# satshakit_modular.net
KiCad netlist of a schematic drawn in EAGLE
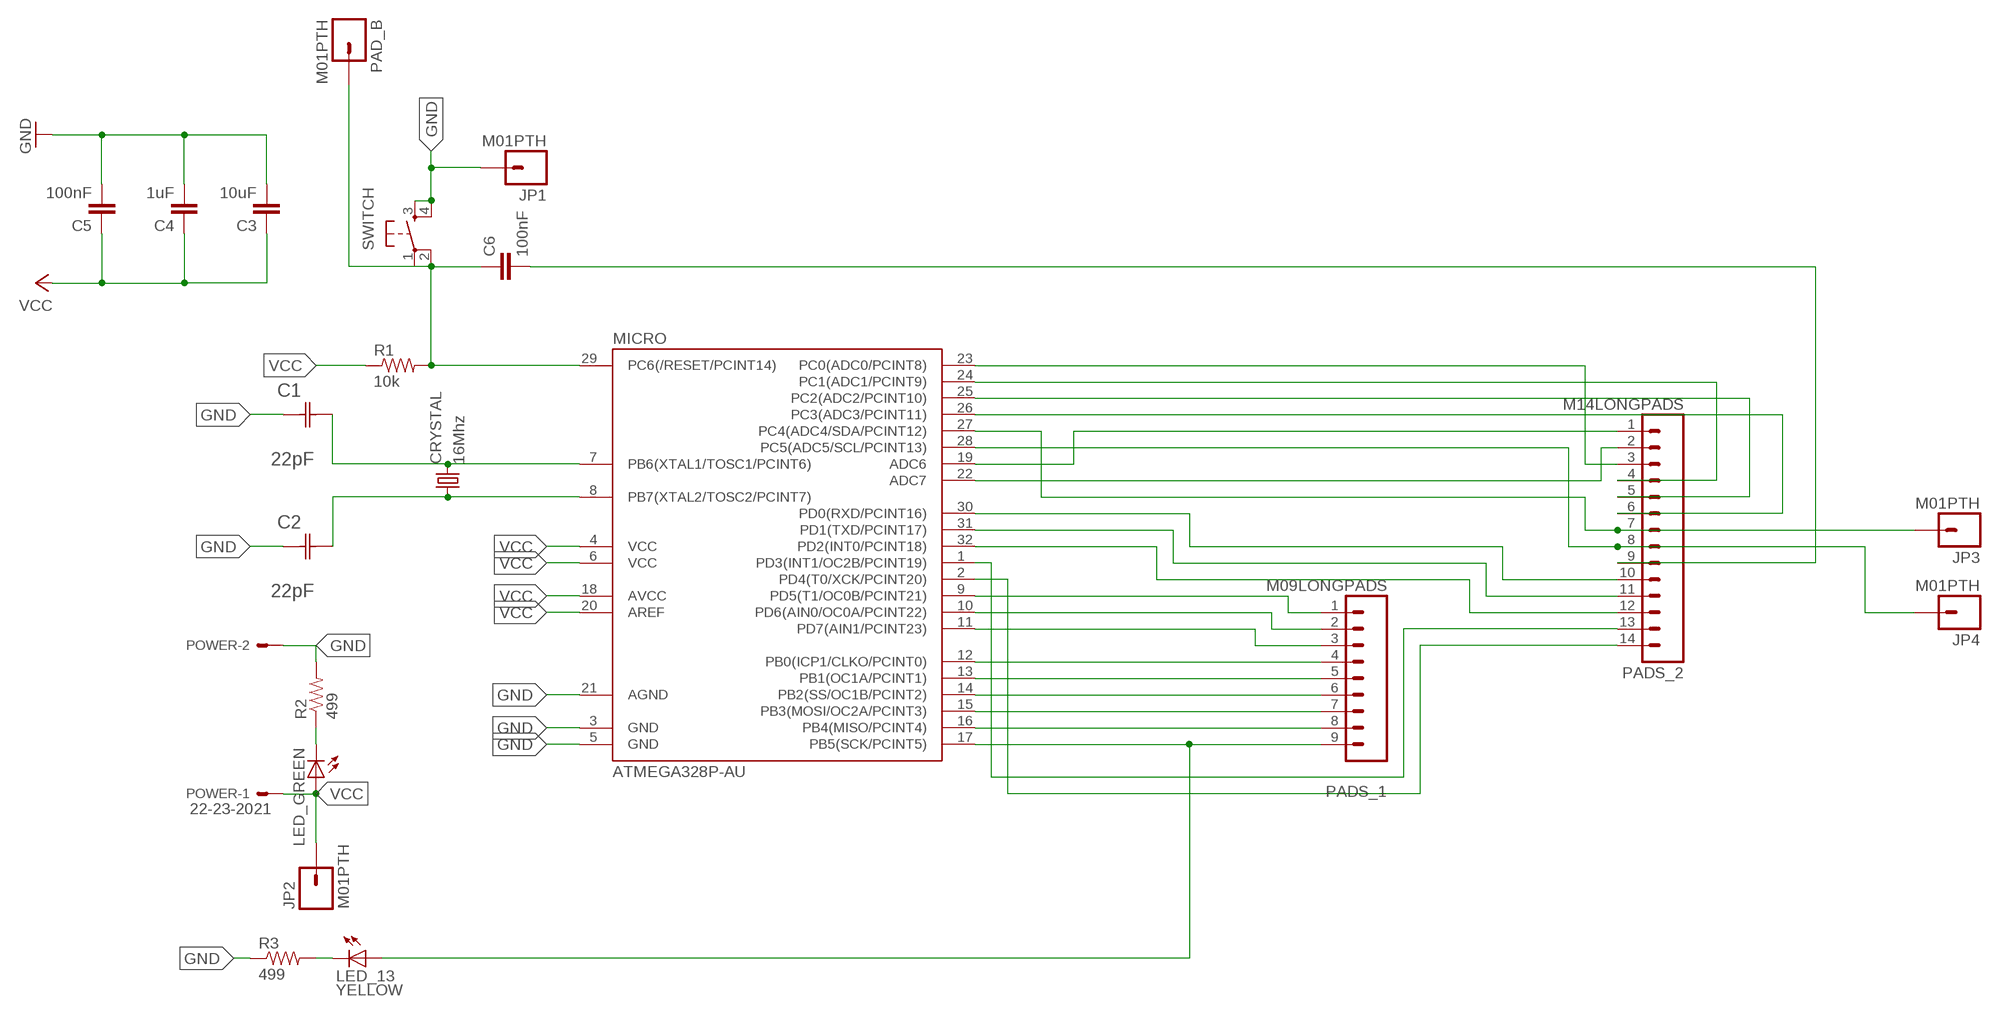
[diagram p0: schematic, sheet 1]

(export (version "E")
  (design (tool "Eeschema 10.0.6"))
  (components
    (comp (ref "C1")
      (value "22pF")
      (footprint "eagle-import:CAPC3216X178N")
      (fields (field (name "MPN") "0612ZC225MAT2A") (field (name "TOLERANCE") "±20%"))
      (libsource (lib "eagle-import") (part "0612ZC225MAT2A"))
    )
    (comp (ref "C2")
      (value "22pF")
      (footprint "eagle-import:CAPC3216X178N")
      (fields (field (name "MPN") "0612ZC225MAT2A") (field (name "TOLERANCE") "±20%"))
      (libsource (lib "eagle-import") (part "0612ZC225MAT2A"))
    )
    (comp (ref "C3")
      (value "10uF")
      (footprint "eagle-import:1206")
      (libsource (lib "eagle-import") (part "CAP1206"))
    )
    (comp (ref "C4")
      (value "1uF")
      (footprint "eagle-import:1206")
      (libsource (lib "eagle-import") (part "CAP1206"))
    )
    (comp (ref "C5")
      (value "100nF")
      (footprint "eagle-import:1206")
      (libsource (lib "eagle-import") (part "CAP1206"))
    )
    (comp (ref "C6")
      (value "100nF")
      (footprint "eagle-import:1206")
      (libsource (lib "eagle-import") (part "CAP1206"))
    )
    (comp (ref "CRYSTAL")
      (value "16Mhz")
      (footprint "eagle-import:CSM-7X-DU")
      (libsource (lib "eagle-import") (part "CSM-7X-DU"))
    )
    (comp (ref "JP1")
      (value "M01PTH")
      (footprint "eagle-import:1X01")
      (libsource (lib "eagle-import") (part "M01PTH"))
    )
    (comp (ref "JP2")
      (value "M01PTH")
      (footprint "eagle-import:1X01")
      (libsource (lib "eagle-import") (part "M01PTH"))
    )
    (comp (ref "JP3")
      (value "M01PTH")
      (footprint "eagle-import:1X01")
      (libsource (lib "eagle-import") (part "M01PTH"))
    )
    (comp (ref "JP4")
      (value "M01PTH")
      (footprint "eagle-import:1X01")
      (libsource (lib "eagle-import") (part "M01PTH"))
    )
    (comp (ref "LED_13")
      (value "YELLOW")
      (footprint "eagle-import:1206")
      (libsource (lib "eagle-import") (part "LED1206"))
    )
    (comp (ref "LED_GREEN")
      (value "LED1206")
      (footprint "eagle-import:1206")
      (libsource (lib "eagle-import") (part "LED1206"))
    )
    (comp (ref "MICRO")
      (value "ATMEGA328P-AU")
      (footprint "eagle-import:TQFP32-08")
      (libsource (lib "eagle-import") (part "ATMEGA48/88/168-AU"))
    )
    (comp (ref "PADS_1")
      (value "M09LONGPADS")
      (footprint "eagle-import:1X09_LONGPADS")
      (libsource (lib "eagle-import") (part "M09LONGPADS"))
    )
    (comp (ref "PADS_2")
      (value "M14LONGPADS")
      (footprint "eagle-import:1X14-LONGPADS")
      (libsource (lib "eagle-import") (part "M14LONGPADS"))
    )
    (comp (ref "PAD_B")
      (value "M01PTH")
      (footprint "eagle-import:1X01")
      (libsource (lib "eagle-import") (part "M01PTH"))
    )
    (comp (ref "POWER")
      (value "22-23-2021")
      (footprint "eagle-import:22-23-2021")
      (fields (field (name "MF") "MOLEX"))
      (libsource (lib "eagle-import") (part "22-23-2021"))
    )
    (comp (ref "R1")
      (value "10k")
      (footprint "eagle-import:1206")
      (libsource (lib "eagle-import") (part "RESISTOR1206"))
    )
    (comp (ref "R2")
      (value "499")
      (footprint "eagle-import:1206")
      (libsource (lib "eagle-import") (part "RESISTOR1206"))
    )
    (comp (ref "R3")
      (value "499")
      (footprint "eagle-import:1206")
      (libsource (lib "eagle-import") (part "RESISTOR1206"))
    )
    (comp (ref "SWITCH")
      (value "6MM_SWITCH6MM_SWITCH")
      (footprint "eagle-import:6MM_SWITCH")
      (libsource (lib "eagle-import") (part "6MM_SWITCH6MM_SWITCH"))
    )
  )
  (nets
    (net (code "1") (name "GND") (class "Default")
      (node (ref "C1") (pin "1") (pinfunction "C1_1") (pintype "passive"))
      (node (ref "C2") (pin "1") (pinfunction "C1_1") (pintype "passive"))
      (node (ref "C3") (pin "2") (pinfunction "2_2") (pintype "passive"))
      (node (ref "C4") (pin "2") (pinfunction "2_2") (pintype "passive"))
      (node (ref "C5") (pin "2") (pinfunction "2_2") (pintype "passive"))
      (node (ref "JP1") (pin "1") (pinfunction "1_1") (pintype "passive"))
      (node (ref "MICRO") (pin "21") (pinfunction "AGND_21") (pintype "power_in"))
      (node (ref "MICRO") (pin "3") (pinfunction "GND_3") (pintype "power_in"))
      (node (ref "MICRO") (pin "5") (pinfunction "GND_5") (pintype "power_in"))
      (node (ref "POWER") (pin "2") (pinfunction "S_2") (pintype "passive"))
      (node (ref "R2") (pin "2") (pinfunction "2_2") (pintype "passive"))
      (node (ref "R3") (pin "1") (pinfunction "1_1") (pintype "passive"))
      (node (ref "SWITCH") (pin "3") (pinfunction "S_3") (pintype "passive"))
      (node (ref "SWITCH") (pin "4") (pinfunction "S1_4") (pintype "passive"))
    )
    (net (code "2") (name "Net-(C1-C2)") (class "Default")
      (node (ref "C1") (pin "2") (pinfunction "C2_2") (pintype "passive"))
      (node (ref "CRYSTAL") (pin "2") (pinfunction "2_2") (pintype "passive"))
      (node (ref "MICRO") (pin "7") (pinfunction "PB6(XTAL1/TOSC1/PCINT6)_7") (pintype "bidirectional"))
    )
    (net (code "3") (name "Net-(C2-C2)") (class "Default")
      (node (ref "C2") (pin "2") (pinfunction "C2_2") (pintype "passive"))
      (node (ref "CRYSTAL") (pin "1") (pinfunction "1_1") (pintype "passive"))
      (node (ref "MICRO") (pin "8") (pinfunction "PB7(XTAL2/TOSC2/PCINT7)_8") (pintype "bidirectional"))
    )
    (net (code "4") (name "Net-(C6-Pad2)") (class "Default")
      (node (ref "C6") (pin "2") (pinfunction "2_2") (pintype "passive"))
      (node (ref "PADS_2") (pin "9") (pinfunction "9_9") (pintype "passive"))
    )
    (net (code "5") (name "Net-(LED_13-A)") (class "Default")
      (node (ref "LED_13") (pin "1") (pinfunction "A_1") (pintype "passive"))
      (node (ref "MICRO") (pin "17") (pinfunction "PB5(SCK/PCINT5)_17") (pintype "bidirectional"))
      (node (ref "PADS_1") (pin "9") (pinfunction "9_9") (pintype "passive"))
    )
    (net (code "6") (name "Net-(LED_13-C)") (class "Default")
      (node (ref "LED_13") (pin "2") (pinfunction "C_2") (pintype "passive"))
      (node (ref "R3") (pin "2") (pinfunction "2_2") (pintype "passive"))
    )
    (net (code "7") (name "Net-(LED_GREEN-C)") (class "Default")
      (node (ref "LED_GREEN") (pin "2") (pinfunction "C_2") (pintype "passive"))
      (node (ref "R2") (pin "1") (pinfunction "1_1") (pintype "passive"))
    )
    (net (code "8") (name "Net-(MICRO-ADC6)") (class "Default")
      (node (ref "MICRO") (pin "19") (pinfunction "ADC6_19") (pintype "passive"))
      (node (ref "PADS_2") (pin "1") (pinfunction "1_1") (pintype "passive"))
    )
    (net (code "9") (name "Net-(MICRO-ADC7)") (class "Default")
      (node (ref "MICRO") (pin "22") (pinfunction "ADC7_22") (pintype "passive"))
      (node (ref "PADS_2") (pin "2") (pinfunction "2_2") (pintype "passive"))
    )
    (net (code "10") (name "Net-(MICRO-PB0(ICP1{slash}CLKO{slash}PCINT0))") (class "Default")
      (node (ref "MICRO") (pin "12") (pinfunction "PB0(ICP1/CLKO/PCINT0)_12") (pintype "bidirectional"))
      (node (ref "PADS_1") (pin "4") (pinfunction "4_4") (pintype "passive"))
    )
    (net (code "11") (name "Net-(MICRO-PB1(OC1A{slash}PCINT1))") (class "Default")
      (node (ref "MICRO") (pin "13") (pinfunction "PB1(OC1A/PCINT1)_13") (pintype "bidirectional"))
      (node (ref "PADS_1") (pin "5") (pinfunction "5_5") (pintype "passive"))
    )
    (net (code "12") (name "Net-(MICRO-PB2(SS{slash}OC1B{slash}PCINT2))") (class "Default")
      (node (ref "MICRO") (pin "14") (pinfunction "PB2(SS/OC1B/PCINT2)_14") (pintype "bidirectional"))
      (node (ref "PADS_1") (pin "6") (pinfunction "6_6") (pintype "passive"))
    )
    (net (code "13") (name "Net-(MICRO-PB3(MOSI{slash}OC2A{slash}PCINT3))") (class "Default")
      (node (ref "MICRO") (pin "15") (pinfunction "PB3(MOSI/OC2A/PCINT3)_15") (pintype "bidirectional"))
      (node (ref "PADS_1") (pin "7") (pinfunction "7_7") (pintype "passive"))
    )
    (net (code "14") (name "Net-(MICRO-PB4(MISO{slash}PCINT4))") (class "Default")
      (node (ref "MICRO") (pin "16") (pinfunction "PB4(MISO/PCINT4)_16") (pintype "bidirectional"))
      (node (ref "PADS_1") (pin "8") (pinfunction "8_8") (pintype "passive"))
    )
    (net (code "15") (name "Net-(MICRO-PC0(ADC0{slash}PCINT8))") (class "Default")
      (node (ref "MICRO") (pin "23") (pinfunction "PC0(ADC0/PCINT8)_23") (pintype "bidirectional"))
      (node (ref "PADS_2") (pin "3") (pinfunction "3_3") (pintype "passive"))
    )
    (net (code "16") (name "Net-(MICRO-PC1(ADC1{slash}PCINT9))") (class "Default")
      (node (ref "MICRO") (pin "24") (pinfunction "PC1(ADC1/PCINT9)_24") (pintype "bidirectional"))
      (node (ref "PADS_2") (pin "4") (pinfunction "4_4") (pintype "passive"))
    )
    (net (code "17") (name "Net-(MICRO-PC2(ADC2{slash}PCINT10))") (class "Default")
      (node (ref "MICRO") (pin "25") (pinfunction "PC2(ADC2/PCINT10)_25") (pintype "bidirectional"))
      (node (ref "PADS_2") (pin "5") (pinfunction "5_5") (pintype "passive"))
    )
    (net (code "18") (name "Net-(MICRO-PC3(ADC3{slash}PCINT11))") (class "Default")
      (node (ref "MICRO") (pin "26") (pinfunction "PC3(ADC3/PCINT11)_26") (pintype "bidirectional"))
      (node (ref "PADS_2") (pin "6") (pinfunction "6_6") (pintype "passive"))
    )
    (net (code "19") (name "Net-(MICRO-PC4(ADC4{slash}SDA{slash}PCINT12))") (class "Default")
      (node (ref "JP3") (pin "1") (pinfunction "1_1") (pintype "passive"))
      (node (ref "MICRO") (pin "27") (pinfunction "PC4(ADC4/SDA/PCINT12)_27") (pintype "bidirectional"))
      (node (ref "PADS_2") (pin "7") (pinfunction "7_7") (pintype "passive"))
    )
    (net (code "20") (name "Net-(MICRO-PC5(ADC5{slash}SCL{slash}PCINT13))") (class "Default")
      (node (ref "JP4") (pin "1") (pinfunction "1_1") (pintype "passive"))
      (node (ref "MICRO") (pin "28") (pinfunction "PC5(ADC5/SCL/PCINT13)_28") (pintype "bidirectional"))
      (node (ref "PADS_2") (pin "8") (pinfunction "8_8") (pintype "passive"))
    )
    (net (code "21") (name "Net-(MICRO-PC6({slash}RESET{slash}PCINT14))") (class "Default")
      (node (ref "C6") (pin "1") (pinfunction "1_1") (pintype "passive"))
      (node (ref "MICRO") (pin "29") (pinfunction "PC6(/RESET/PCINT14)_29") (pintype "bidirectional"))
      (node (ref "PAD_B") (pin "1") (pinfunction "1_1") (pintype "passive"))
      (node (ref "R1") (pin "2") (pinfunction "2_2") (pintype "passive"))
      (node (ref "SWITCH") (pin "1") (pinfunction "P_1") (pintype "passive"))
      (node (ref "SWITCH") (pin "2") (pinfunction "P1_2") (pintype "passive"))
    )
    (net (code "22") (name "Net-(MICRO-PD0(RXD{slash}PCINT16))") (class "Default")
      (node (ref "MICRO") (pin "30") (pinfunction "PD0(RXD/PCINT16)_30") (pintype "bidirectional"))
      (node (ref "PADS_2") (pin "10") (pinfunction "10_10") (pintype "passive"))
    )
    (net (code "23") (name "Net-(MICRO-PD1(TXD{slash}PCINT17))") (class "Default")
      (node (ref "MICRO") (pin "31") (pinfunction "PD1(TXD/PCINT17)_31") (pintype "bidirectional"))
      (node (ref "PADS_2") (pin "11") (pinfunction "11_11") (pintype "passive"))
    )
    (net (code "24") (name "Net-(MICRO-PD2(INT0{slash}PCINT18))") (class "Default")
      (node (ref "MICRO") (pin "32") (pinfunction "PD2(INT0/PCINT18)_32") (pintype "bidirectional"))
      (node (ref "PADS_2") (pin "12") (pinfunction "12_12") (pintype "passive"))
    )
    (net (code "25") (name "Net-(MICRO-PD3(INT1{slash}OC2B{slash}PCINT19))") (class "Default")
      (node (ref "MICRO") (pin "1") (pinfunction "PD3(INT1/OC2B/PCINT19)_1") (pintype "bidirectional"))
      (node (ref "PADS_2") (pin "13") (pinfunction "13_13") (pintype "passive"))
    )
    (net (code "26") (name "Net-(MICRO-PD4(T0{slash}XCK{slash}PCINT20))") (class "Default")
      (node (ref "MICRO") (pin "2") (pinfunction "PD4(T0/XCK/PCINT20)_2") (pintype "bidirectional"))
      (node (ref "PADS_2") (pin "14") (pinfunction "14_14") (pintype "passive"))
    )
    (net (code "27") (name "Net-(MICRO-PD5(T1{slash}OC0B{slash}PCINT21))") (class "Default")
      (node (ref "MICRO") (pin "9") (pinfunction "PD5(T1/OC0B/PCINT21)_9") (pintype "bidirectional"))
      (node (ref "PADS_1") (pin "1") (pinfunction "1_1") (pintype "passive"))
    )
    (net (code "28") (name "Net-(MICRO-PD6(AIN0{slash}OC0A{slash}PCINT22))") (class "Default")
      (node (ref "MICRO") (pin "10") (pinfunction "PD6(AIN0/OC0A/PCINT22)_10") (pintype "bidirectional"))
      (node (ref "PADS_1") (pin "2") (pinfunction "2_2") (pintype "passive"))
    )
    (net (code "29") (name "Net-(MICRO-PD7(AIN1{slash}PCINT23))") (class "Default")
      (node (ref "MICRO") (pin "11") (pinfunction "PD7(AIN1/PCINT23)_11") (pintype "bidirectional"))
      (node (ref "PADS_1") (pin "3") (pinfunction "3_3") (pintype "passive"))
    )
    (net (code "30") (name "VCC") (class "Default")
      (node (ref "C3") (pin "1") (pinfunction "1_1") (pintype "passive"))
      (node (ref "C4") (pin "1") (pinfunction "1_1") (pintype "passive"))
      (node (ref "C5") (pin "1") (pinfunction "1_1") (pintype "passive"))
      (node (ref "JP2") (pin "1") (pinfunction "1_1") (pintype "passive"))
      (node (ref "LED_GREEN") (pin "1") (pinfunction "A_1") (pintype "passive"))
      (node (ref "MICRO") (pin "18") (pinfunction "AVCC_18") (pintype "passive"))
      (node (ref "MICRO") (pin "20") (pinfunction "AREF_20") (pintype "passive"))
      (node (ref "MICRO") (pin "4") (pinfunction "VCC_4") (pintype "power_in"))
      (node (ref "MICRO") (pin "6") (pinfunction "VCC_6") (pintype "power_in"))
      (node (ref "POWER") (pin "1") (pinfunction "S_1") (pintype "passive"))
      (node (ref "R1") (pin "1") (pinfunction "1_1") (pintype "passive"))
    )
  )
)
